# board.net
KiCad netlist of a schematic drawn in EAGLE
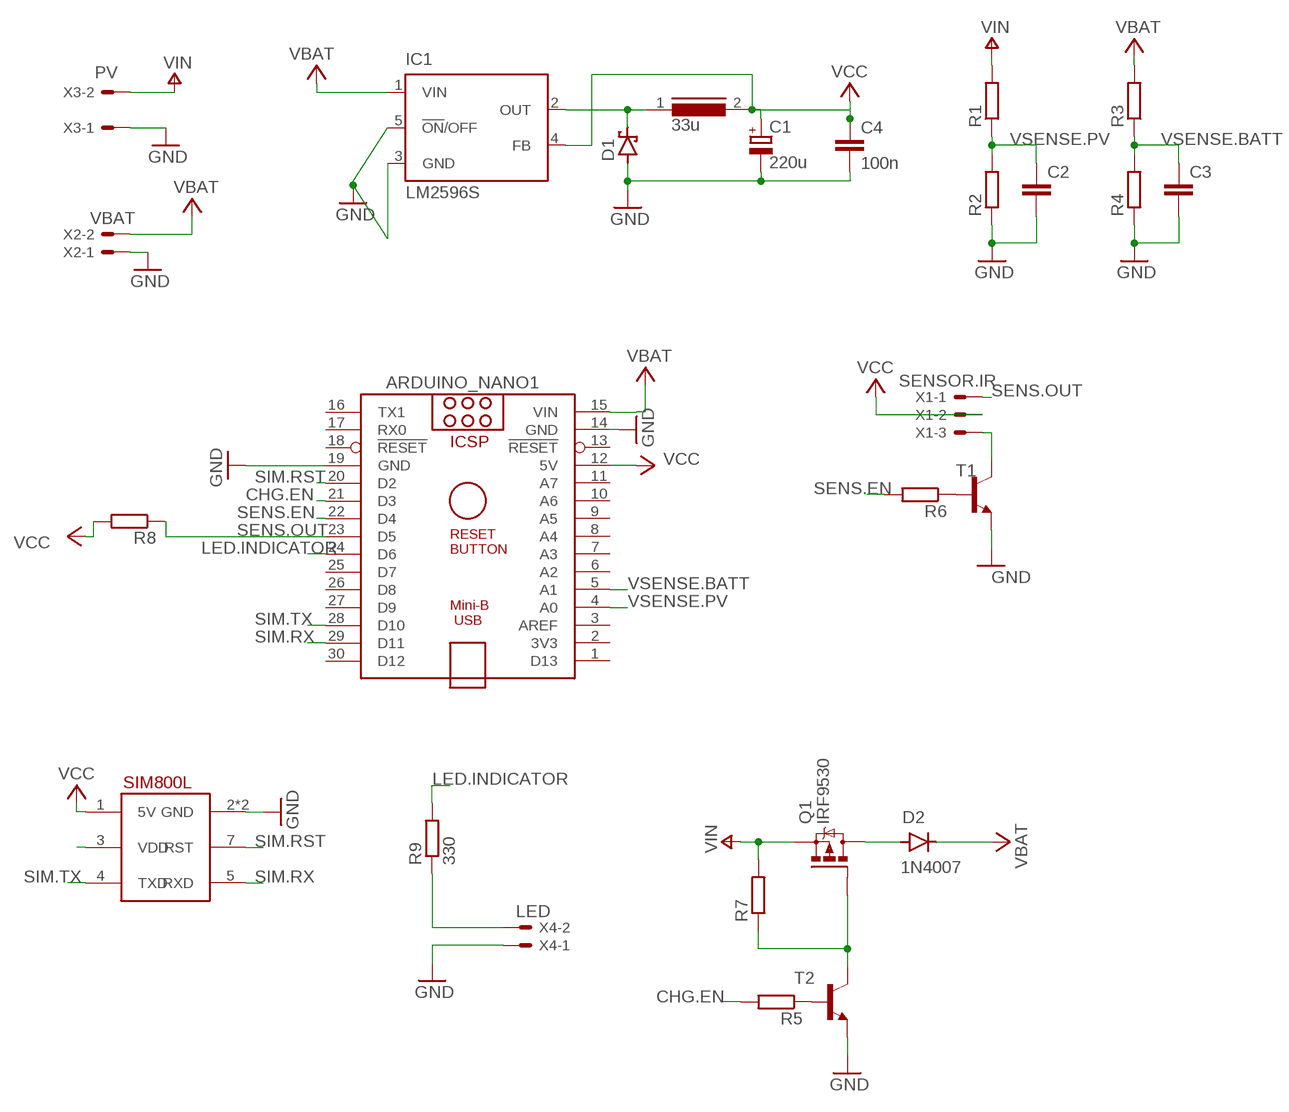
[diagram p0: schematic, sheet 1]

(export (version "E")
  (design (tool "Eeschema 10.0.6"))
  (components
    (comp (ref "ARDUINO_NANO1")
      (value "ARDUINO_NANO")
      (footprint "eagle-import:ARDUINO_NANO")
      (libsource (lib "eagle-import") (part "ARDUINO_NANO"))
    )
    (comp (ref "C1")
      (value "220u")
      (footprint "eagle-import:153CLV-0810")
      (libsource (lib "eagle-import") (part "CPOL-EU153CLV-0810"))
    )
    (comp (ref "C2")
      (value "C-EUC0805")
      (footprint "eagle-import:C0805")
      (libsource (lib "eagle-import") (part "C-EUC0805"))
    )
    (comp (ref "C3")
      (value "C-EUC0805")
      (footprint "eagle-import:C0805")
      (libsource (lib "eagle-import") (part "C-EUC0805"))
    )
    (comp (ref "C4")
      (value "100n")
      (footprint "eagle-import:C0805")
      (libsource (lib "eagle-import") (part "C-EUC0805"))
    )
    (comp (ref "D1")
      (value "SCHOTTKY-DIODESMD")
      (footprint "eagle-import:SMB")
      (libsource (lib "eagle-import") (part "SCHOTTKY-DIODESMD"))
    )
    (comp (ref "D2")
      (value "1N4007")
      (footprint "eagle-import:DO-41")
      (fields
        (field (name "DIGIKEY_PART_NUMBER") "1N4007MSCT-ND")
        (field (name "MANUFACTURER") "Micro Commercial Co")
        (field (name "CREATED_BY") "PCBLayout.com")
      )
      (libsource (lib "eagle-import") (part "1N4007"))
    )
    (comp (ref "IC1")
      (value "LM2596S")
      (footprint "eagle-import:TO263-5")
      (fields (field (name "MF") "NATIONAL SEMICONDUCTOR") (field (name "MPN") "LM2596S-ADJ/NOPB"))
      (libsource (lib "eagle-import") (part "LM2596S"))
    )
    (comp (ref "L2")
      (value "33u")
      (footprint "eagle-import:DR125")
      (libsource (lib "eagle-import") (part "DR125"))
    )
    (comp (ref "Q1")
      (value "IRF9530")
      (footprint "eagle-import:TO220BV")
      (libsource (lib "eagle-import") (part "IRF9530"))
    )
    (comp (ref "R1")
      (value "R-EU_R0805")
      (footprint "eagle-import:R0805")
      (libsource (lib "eagle-import") (part "R-EU_R0805"))
    )
    (comp (ref "R2")
      (value "R-EU_R0805")
      (footprint "eagle-import:R0805")
      (libsource (lib "eagle-import") (part "R-EU_R0805"))
    )
    (comp (ref "R3")
      (value "R-EU_R0805")
      (footprint "eagle-import:R0805")
      (libsource (lib "eagle-import") (part "R-EU_R0805"))
    )
    (comp (ref "R4")
      (value "R-EU_R0805")
      (footprint "eagle-import:R0805")
      (libsource (lib "eagle-import") (part "R-EU_R0805"))
    )
    (comp (ref "R5")
      (value "R-EU_0207/7")
      (footprint "eagle-import:0207_7")
      (libsource (lib "eagle-import") (part "R-EU_0207/7"))
    )
    (comp (ref "R6")
      (value "R-EU_0207/7")
      (footprint "eagle-import:0207_7")
      (libsource (lib "eagle-import") (part "R-EU_0207/7"))
    )
    (comp (ref "R7")
      (value "R-EU_0207/7")
      (footprint "eagle-import:0207_7")
      (libsource (lib "eagle-import") (part "R-EU_0207/7"))
    )
    (comp (ref "R8")
      (value "R-EU_0207/7")
      (footprint "eagle-import:0207_7")
      (libsource (lib "eagle-import") (part "R-EU_0207/7"))
    )
    (comp (ref "R9")
      (value "330")
      (footprint "eagle-import:R0805")
      (libsource (lib "eagle-import") (part "R-EU_R0805"))
    )
    (comp (ref "T1")
      (value "-NPN-TO92-ECB")
      (footprint "eagle-import:TO92-ECB")
      (libsource (lib "eagle-import") (part "-NPN-TO92-ECB"))
    )
    (comp (ref "T2")
      (value "-NPN-TO92-ECB")
      (footprint "eagle-import:TO92-ECB")
      (libsource (lib "eagle-import") (part "-NPN-TO92-ECB"))
    )
    (comp (ref "U$1")
      (value "SIM800L")
      (footprint "eagle-import:SIP")
      (libsource (lib "eagle-import") (part "SIM800L"))
    )
    (comp (ref "X1")
      (value "SENSOR.IR")
      (footprint "eagle-import:JST-XH-03-PACKAGE-LONG-PAD")
      (libsource (lib "eagle-import") (part "JST-XH-03-PIN-LONG-PAD"))
    )
    (comp (ref "X2")
      (value "VBAT")
      (footprint "eagle-import:JST-XH-02-PACKAGE-LONG-PAD")
      (libsource (lib "eagle-import") (part "JST-XH-02-PIN-LONG-PAD"))
    )
    (comp (ref "X3")
      (value "PV")
      (footprint "eagle-import:KK-156-2")
      (fields (field (name "MF") "MOLEX"))
      (libsource (lib "eagle-import") (part "KK-156-2"))
    )
    (comp (ref "X4")
      (value "LED")
      (footprint "eagle-import:JST-XH-02-PACKAGE-LONG-PAD")
      (libsource (lib "eagle-import") (part "JST-XH-02-PIN-LONG-PAD"))
    )
  )
  (nets
    (net (code "1") (name "+5V") (class "Default")
      (node (ref "ARDUINO_NANO1") (pin "15") (pinfunction "VIN_15") (pintype "power_in"))
      (node (ref "D2") (pin "C") (pinfunction "C_C") (pintype "passive"))
      (node (ref "IC1") (pin "1") (pinfunction "VIN_1") (pintype "input"))
      (node (ref "R3") (pin "2") (pinfunction "2_2") (pintype "passive"))
      (node (ref "X2") (pin "2") (pinfunction "S_2") (pintype "passive"))
    )
    (net (code "2") (name "CHG.EN") (class "Default")
      (node (ref "ARDUINO_NANO1") (pin "21") (pinfunction "D3_21") (pintype "bidirectional"))
      (node (ref "R5") (pin "2") (pinfunction "2_2") (pintype "passive"))
    )
    (net (code "3") (name "GND") (class "Default")
      (node (ref "ARDUINO_NANO1") (pin "14") (pinfunction "GND_14") (pintype "power_in"))
      (node (ref "ARDUINO_NANO1") (pin "19") (pinfunction "GND_19") (pintype "power_in"))
      (node (ref "C1") (pin "-") (pinfunction "-_-") (pintype "passive"))
      (node (ref "C2") (pin "2") (pinfunction "2_2") (pintype "passive"))
      (node (ref "C3") (pin "2") (pinfunction "2_2") (pintype "passive"))
      (node (ref "C4") (pin "2") (pinfunction "2_2") (pintype "passive"))
      (node (ref "D1") (pin "A") (pinfunction "A_A") (pintype "passive"))
      (node (ref "IC1") (pin "3") (pinfunction "GND_3") (pintype "power_in"))
      (node (ref "IC1") (pin "5") (pinfunction "~{ON}/OFF_5") (pintype "input"))
      (node (ref "R2") (pin "1") (pinfunction "1_1") (pintype "passive"))
      (node (ref "R4") (pin "1") (pinfunction "1_1") (pintype "passive"))
      (node (ref "T1") (pin "E") (pinfunction "E_E") (pintype "passive"))
      (node (ref "T2") (pin "E") (pinfunction "E_E") (pintype "passive"))
      (node (ref "U$1") (pin "2") (pinfunction "GND_2") (pintype "bidirectional"))
      (node (ref "U$1") (pin "6") (pinfunction "GND_6") (pintype "bidirectional"))
      (node (ref "X2") (pin "1") (pinfunction "S_1") (pintype "passive"))
      (node (ref "X3") (pin "1") (pinfunction "S_1") (pintype "passive"))
      (node (ref "X4") (pin "1") (pinfunction "S_1") (pintype "passive"))
    )
    (net (code "4") (name "LED.INDICATOR") (class "Default")
      (node (ref "ARDUINO_NANO1") (pin "24") (pinfunction "D6_24") (pintype "bidirectional"))
      (node (ref "R9") (pin "2") (pinfunction "2_2") (pintype "passive"))
    )
    (net (code "5") (name "Net-(D2-PadA)") (class "Default")
      (node (ref "D2") (pin "A") (pinfunction "A_A") (pintype "passive"))
      (node (ref "Q1") (pin "D") (pinfunction "D_D") (pintype "passive"))
    )
    (net (code "6") (name "Net-(IC1-OUT)") (class "Default")
      (node (ref "D1") (pin "C") (pinfunction "C_C") (pintype "passive"))
      (node (ref "IC1") (pin "2") (pinfunction "OUT_2") (pintype "output"))
      (node (ref "L2") (pin "1") (pinfunction "1_1") (pintype "passive"))
    )
    (net (code "7") (name "Net-(Q1-PadG)") (class "Default")
      (node (ref "Q1") (pin "G") (pinfunction "G_G") (pintype "passive"))
      (node (ref "R7") (pin "1") (pinfunction "1_1") (pintype "passive"))
      (node (ref "T2") (pin "C") (pinfunction "C_C") (pintype "passive"))
    )
    (net (code "8") (name "Net-(R5-Pad1)") (class "Default")
      (node (ref "R5") (pin "1") (pinfunction "1_1") (pintype "passive"))
      (node (ref "T2") (pin "B") (pinfunction "B_B") (pintype "passive"))
    )
    (net (code "9") (name "Net-(R6-Pad1)") (class "Default")
      (node (ref "R6") (pin "1") (pinfunction "1_1") (pintype "passive"))
      (node (ref "T1") (pin "B") (pinfunction "B_B") (pintype "passive"))
    )
    (net (code "10") (name "Net-(X1C-S)") (class "Default")
      (node (ref "T1") (pin "C") (pinfunction "C_C") (pintype "passive"))
      (node (ref "X1") (pin "3") (pinfunction "S_3") (pintype "passive"))
    )
    (net (code "11") (name "Net-(X4B-S)") (class "Default")
      (node (ref "R9") (pin "1") (pinfunction "1_1") (pintype "passive"))
      (node (ref "X4") (pin "2") (pinfunction "S_2") (pintype "passive"))
    )
    (net (code "12") (name "SENS.EN") (class "Default")
      (node (ref "ARDUINO_NANO1") (pin "22") (pinfunction "D4_22") (pintype "bidirectional"))
      (node (ref "R6") (pin "2") (pinfunction "2_2") (pintype "passive"))
    )
    (net (code "13") (name "SENS.OUT") (class "Default")
      (node (ref "ARDUINO_NANO1") (pin "23") (pinfunction "D5_23") (pintype "bidirectional"))
      (node (ref "R8") (pin "1") (pinfunction "1_1") (pintype "passive"))
      (node (ref "X1") (pin "1") (pinfunction "S_1") (pintype "passive"))
    )
    (net (code "14") (name "SIM.RST") (class "Default")
      (node (ref "ARDUINO_NANO1") (pin "20") (pinfunction "D2_20") (pintype "bidirectional"))
      (node (ref "U$1") (pin "7") (pinfunction "RST_7") (pintype "bidirectional"))
    )
    (net (code "15") (name "SIM.RX") (class "Default")
      (node (ref "ARDUINO_NANO1") (pin "29") (pinfunction "D11_29") (pintype "bidirectional"))
      (node (ref "U$1") (pin "5") (pinfunction "RXD_5") (pintype "bidirectional"))
    )
    (net (code "16") (name "SIM.TX") (class "Default")
      (node (ref "ARDUINO_NANO1") (pin "28") (pinfunction "D10_28") (pintype "bidirectional"))
      (node (ref "U$1") (pin "4") (pinfunction "TXD_4") (pintype "bidirectional"))
    )
    (net (code "17") (name "V+") (class "Default")
      (node (ref "Q1") (pin "S") (pinfunction "S_S") (pintype "passive"))
      (node (ref "R1") (pin "2") (pinfunction "2_2") (pintype "passive"))
      (node (ref "R7") (pin "2") (pinfunction "2_2") (pintype "passive"))
      (node (ref "X3") (pin "2") (pinfunction "S_2") (pintype "passive"))
    )
    (net (code "18") (name "VCC") (class "Default")
      (node (ref "ARDUINO_NANO1") (pin "12") (pinfunction "5V_12") (pintype "power_in"))
      (node (ref "C1") (pin "+") (pinfunction "+_+") (pintype "passive"))
      (node (ref "C4") (pin "1") (pinfunction "1_1") (pintype "passive"))
      (node (ref "IC1") (pin "4") (pinfunction "FB_4") (pintype "input"))
      (node (ref "L2") (pin "2") (pinfunction "2_2") (pintype "passive"))
      (node (ref "R8") (pin "2") (pinfunction "2_2") (pintype "passive"))
      (node (ref "U$1") (pin "1") (pinfunction "5V_1") (pintype "bidirectional"))
      (node (ref "X1") (pin "2") (pinfunction "S_2") (pintype "passive"))
    )
    (net (code "19") (name "VSENSE.BATT") (class "Default")
      (node (ref "ARDUINO_NANO1") (pin "5") (pinfunction "A1_5") (pintype "bidirectional"))
      (node (ref "C3") (pin "1") (pinfunction "1_1") (pintype "passive"))
      (node (ref "R3") (pin "1") (pinfunction "1_1") (pintype "passive"))
      (node (ref "R4") (pin "2") (pinfunction "2_2") (pintype "passive"))
    )
    (net (code "20") (name "VSENSE.PV") (class "Default")
      (node (ref "ARDUINO_NANO1") (pin "4") (pinfunction "A0_4") (pintype "bidirectional"))
      (node (ref "C2") (pin "1") (pinfunction "1_1") (pintype "passive"))
      (node (ref "R1") (pin "1") (pinfunction "1_1") (pintype "passive"))
      (node (ref "R2") (pin "2") (pinfunction "2_2") (pintype "passive"))
    )
    (net (code "21") (name "unconnected-(ARDUINO_NANO1-3V3-Pad2)") (class "Default")
      (node (ref "ARDUINO_NANO1") (pin "2") (pinfunction "3V3_2") (pintype "output"))
    )
    (net (code "22") (name "unconnected-(ARDUINO_NANO1-A2-Pad6)") (class "Default")
      (node (ref "ARDUINO_NANO1") (pin "6") (pinfunction "A2_6") (pintype "bidirectional"))
    )
    (net (code "23") (name "unconnected-(ARDUINO_NANO1-A3-Pad7)") (class "Default")
      (node (ref "ARDUINO_NANO1") (pin "7") (pinfunction "A3_7") (pintype "bidirectional"))
    )
    (net (code "24") (name "unconnected-(ARDUINO_NANO1-A4-Pad8)") (class "Default")
      (node (ref "ARDUINO_NANO1") (pin "8") (pinfunction "A4_8") (pintype "bidirectional"))
    )
    (net (code "25") (name "unconnected-(ARDUINO_NANO1-A5-Pad9)") (class "Default")
      (node (ref "ARDUINO_NANO1") (pin "9") (pinfunction "A5_9") (pintype "bidirectional"))
    )
    (net (code "26") (name "unconnected-(ARDUINO_NANO1-A6-Pad10)") (class "Default")
      (node (ref "ARDUINO_NANO1") (pin "10") (pinfunction "A6_10") (pintype "bidirectional"))
    )
    (net (code "27") (name "unconnected-(ARDUINO_NANO1-A7-Pad11)") (class "Default")
      (node (ref "ARDUINO_NANO1") (pin "11") (pinfunction "A7_11") (pintype "bidirectional"))
    )
    (net (code "28") (name "unconnected-(ARDUINO_NANO1-AREF-Pad3)") (class "Default")
      (node (ref "ARDUINO_NANO1") (pin "3") (pinfunction "AREF_3") (pintype "input"))
    )
    (net (code "29") (name "unconnected-(ARDUINO_NANO1-D7-Pad25)") (class "Default")
      (node (ref "ARDUINO_NANO1") (pin "25") (pinfunction "D7_25") (pintype "bidirectional"))
    )
    (net (code "30") (name "unconnected-(ARDUINO_NANO1-D8-Pad26)") (class "Default")
      (node (ref "ARDUINO_NANO1") (pin "26") (pinfunction "D8_26") (pintype "bidirectional"))
    )
    (net (code "31") (name "unconnected-(ARDUINO_NANO1-D9-Pad27)") (class "Default")
      (node (ref "ARDUINO_NANO1") (pin "27") (pinfunction "D9_27") (pintype "bidirectional"))
    )
    (net (code "32") (name "unconnected-(ARDUINO_NANO1-D12-Pad30)") (class "Default")
      (node (ref "ARDUINO_NANO1") (pin "30") (pinfunction "D12_30") (pintype "bidirectional"))
    )
    (net (code "33") (name "unconnected-(ARDUINO_NANO1-D13-Pad1)") (class "Default")
      (node (ref "ARDUINO_NANO1") (pin "1") (pinfunction "D13_1") (pintype "bidirectional"))
    )
    (net (code "34") (name "unconnected-(ARDUINO_NANO1-RX0-Pad17)") (class "Default")
      (node (ref "ARDUINO_NANO1") (pin "17") (pinfunction "RX0_17") (pintype "bidirectional"))
    )
    (net (code "35") (name "unconnected-(ARDUINO_NANO1-TX1-Pad16)") (class "Default")
      (node (ref "ARDUINO_NANO1") (pin "16") (pinfunction "TX1_16") (pintype "bidirectional"))
    )
    (net (code "36") (name "unconnected-(ARDUINO_NANO1-~{RESET}-Pad13)") (class "Default")
      (node (ref "ARDUINO_NANO1") (pin "13") (pinfunction "~{RESET}_13") (pintype "input"))
    )
    (net (code "37") (name "unconnected-(ARDUINO_NANO1-~{RESET}-Pad18)") (class "Default")
      (node (ref "ARDUINO_NANO1") (pin "18") (pinfunction "~{RESET}_18") (pintype "input"))
    )
    (net (code "38") (name "unconnected-(U$1-VDD-Pad3)") (class "Default")
      (node (ref "U$1") (pin "3") (pinfunction "VDD_3") (pintype "bidirectional"))
    )
  )
)
